# 07_MCU.net
KiCad netlist of a schematic drawn in Altium Designer
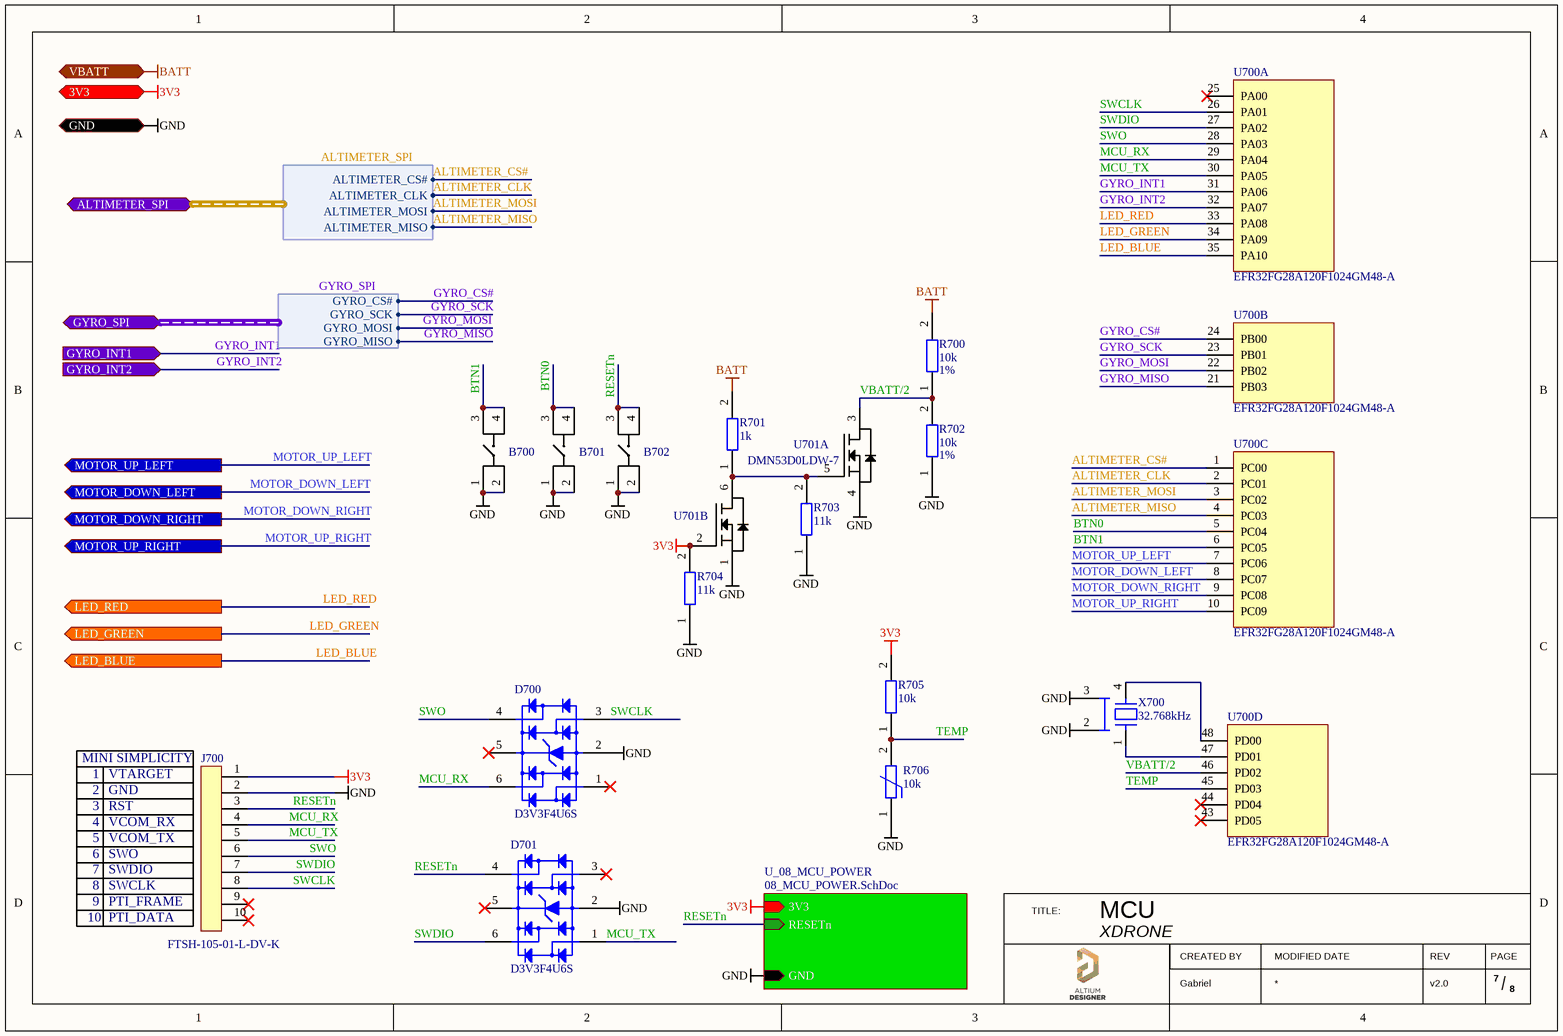
[diagram p0: 07_MCU.SchDoc]

(export (version "E")
  (design (tool "Eeschema 10.0.6"))
  (components
    (comp (ref "B700")
      (value "BTN_1B_PTS647SK38SMTR2LFS")
      (footprint "BTN_SMD")
      (description "Button PTS647SK38SMTR2LFS")
      (fields (field (name "MANUFACTURER") "C&K"))
      (libsource (lib "Connectors") (part "BTN_1B_PTS647SK38SMTR2LFS"))
    )
    (comp (ref "B701")
      (value "BTN_1B_PTS647SK38SMTR2LFS")
      (footprint "BTN_SMD")
      (description "Button PTS647SK38SMTR2LFS")
      (fields (field (name "MANUFACTURER") "C&K"))
      (libsource (lib "Connectors") (part "BTN_1B_PTS647SK38SMTR2LFS"))
    )
    (comp (ref "B702")
      (value "BTN_1B_PTS647SK38SMTR2LFS")
      (footprint "BTN_SMD")
      (description "Button PTS647SK38SMTR2LFS")
      (fields (field (name "MANUFACTURER") "C&K"))
      (libsource (lib "Connectors") (part "BTN_1B_PTS647SK38SMTR2LFS"))
    )
    (comp (ref "D700")
      (value "ESD_D3V3F4U6S")
      (footprint "SOT-363 SC-70-6")
      (description "4 CH ESD PROTECTION SOT363 LOW CAP D3V3F4U6S")
      (fields (field (name "MANUFACTURER") "DIODES INC") (field (name "MANUFACTURER REFERENCE") "D3V3F4U6S"))
      (libsource (lib "Semiconductor") (part "ESD_D3V3F4U6S"))
    )
    (comp (ref "D701")
      (value "ESD_D3V3F4U6S")
      (footprint "SOT-363 SC-70-6")
      (description "4 CH ESD PROTECTION SOT363 LOW CAP D3V3F4U6S")
      (fields (field (name "MANUFACTURER") "DIODES INC") (field (name "MANUFACTURER REFERENCE") "D3V3F4U6S"))
      (libsource (lib "Semiconductor") (part "ESD_D3V3F4U6S"))
    )
    (comp (ref "J700")
      (value "CON_5x2PIN_RA_1.27_FTSH-105-01-L-DV-K")
      (footprint "CON_5x2PIN_RA_FTSH-105-01-L-DV-K")
      (description "CONNECTOR 5x2PIN RA 1.27 PITCH FTSH-105-01-L-DV-K")
      (fields
        (field (name "MANUFACTURER") "SAMTEC")
        (field (name "MANUFACTURER REFERENCE") "FTSH-105-01-L-DV-K")
      )
      (libsource (lib "Connectors") (part "CON_5x2PIN_RA_1.27_FTSH-105-01-L-DV-K"))
    )
    (comp (ref "R700")
      (value "10k")
      (footprint "RES_0402")
      (description "RESISTOR 10k 1% 0402 RC0402FR-0710KL")
      (fields
        (field (name "TOLERANCE") "1%")
        (field (name "MANUFACTURER") "YAGEO")
        (field (name "Comment") "RES_10k_1%_0402_RC0402FR-0710KL")
      )
      (libsource (lib "Resistors") (part "RES_10k_1%_0402_RC0402FR-0710KL"))
    )
    (comp (ref "R701")
      (value "1k")
      (footprint "RES_0402")
      (description "RESISTOR 1k 1% 0402 RC0402FR-071KL")
      (fields (field (name "TOLERANCE") "1%") (field (name "MANUFACTURER") "YAGEO"))
      (libsource (lib "Resistors") (part "RES_1k_1%_0402_RC0402FR-071KL"))
    )
    (comp (ref "R702")
      (value "10k")
      (footprint "RES_0402")
      (description "RESISTOR 10k 1% 0402 RC0402FR-0710KL")
      (fields
        (field (name "TOLERANCE") "1%")
        (field (name "MANUFACTURER") "YAGEO")
        (field (name "Comment") "RES_10k_1%_0402_RC0402FR-0710KL")
      )
      (libsource (lib "Resistors") (part "RES_10k_1%_0402_RC0402FR-0710KL"))
    )
    (comp (ref "R703")
      (value "11k")
      (footprint "RES_0402")
      (description "RESISTOR 11k 5% 0402 ERJ-2GEJ113X")
      (fields (field (name "TOLERANCE") "5%") (field (name "MANUFACTURER") "PANASONIC"))
      (libsource (lib "Resistors") (part "RES_11k_5%_0402_ERJ-2GEJ113X"))
    )
    (comp (ref "R704")
      (value "11k")
      (footprint "RES_0402")
      (description "RESISTOR 11k 5% 0402 ERJ-2GEJ113X")
      (fields (field (name "TOLERANCE") "5%") (field (name "MANUFACTURER") "PANASONIC"))
      (libsource (lib "Resistors") (part "RES_11k_5%_0402_ERJ-2GEJ113X"))
    )
    (comp (ref "R705")
      (value "10k")
      (footprint "RES_0402")
      (description "RESISTOR 10k 1% 0402 RC0402FR-0710KL")
      (fields (field (name "TOLERANCE") "1%") (field (name "MANUFACTURER") "YAGEO"))
      (libsource (lib "Resistors") (part "RES_10k_1%_0402_RC0402FR-0710KL"))
    )
    (comp (ref "R706")
      (value "10k")
      (footprint "RES_0402")
      (description "THERMISTANCE 10k 1% 0402 NTCG103JF103FT1")
      (fields (field (name "TOLERANCE") "1%") (field (name "MANUFACTURER") "TDK"))
      (libsource (lib "Resistors") (part "THER_10k_1%_0402_NTCG103JF103FT1"))
    )
    (comp (ref "U700")
      (value "MCU_1MB_256kB_EFR32FG28A120F1024GM48-A")
      (footprint "QFN48")
      (description "MCU 1MB 256kB EFR32FG28A120F1024GM48-A")
      (fields
        (field (name "MANUFACTURER") "SILICON LABS")
        (field (name "MANUFACTURER REFERENCE") "EFR32FG28A120F1024GM48-A")
      )
      (libsource (lib "Semiconductor") (part "MCU_1MB_256kB_EFR32FG28A120F1024GM48-A"))
    )
    (comp (ref "U701")
      (value "MOS_2G_50VDS_360mA_0.8Vth_DMN53D0LDW-7")
      (footprint "SOT-363 SC-70-6")
      (description "MOS 2GATES 50VDS 360mA 0.8Vth")
      (fields (field (name "MANUFACTURER") "DIODES") (field (name "MANUFACTURER REFERENCE") "DMN53D0LDW-7"))
      (libsource (lib "Semiconductor") (part "MOS_2G_50VDS_360mA_0.8Vth_DMN53D0LDW-7"))
    )
    (comp (ref "X700")
      (value "QUARTZ_32.768kHz_20ppm_830016178")
      (footprint "4-SOJ")
      (description "QUARTZ 32.768kHz 20ppm 830016178")
      (fields
        (field (name "MANUFACTURER") "WURTH")
        (field (name "TOLERANCE") "20 ppm")
        (field (name "FREQUENCY") "32.768kHz")
      )
      (libsource (lib "Oscillators") (part "QUARTZ_32.768kHz_20ppm_830016178"))
    )
  )
  (nets
    (net (code "3") (name "/ALTIMETER_CLK") (class "Default")
      (node (ref "U700") (pin "2") (pinfunction "PC01_2") (pintype "passive"))
    )
    (net (code "4") (name "/ALTIMETER_CS#") (class "Default")
      (node (ref "U700") (pin "1") (pinfunction "PC00_1") (pintype "passive"))
    )
    (net (code "5") (name "/ALTIMETER_MISO") (class "Default")
      (node (ref "U700") (pin "4") (pinfunction "PC03_4") (pintype "passive"))
    )
    (net (code "6") (name "/ALTIMETER_MOSI") (class "Default")
      (node (ref "U700") (pin "3") (pinfunction "PC02_3") (pintype "passive"))
    )
    (net (code "7") (name "/BTN0") (class "Default")
      (node (ref "B701") (pin "3") (pintype "passive"))
      (node (ref "B701") (pin "4") (pintype "passive"))
      (node (ref "U700") (pin "5") (pinfunction "PC04_5") (pintype "passive"))
    )
    (net (code "8") (name "/BTN1") (class "Default")
      (node (ref "B700") (pin "3") (pintype "passive"))
      (node (ref "B700") (pin "4") (pintype "passive"))
      (node (ref "U700") (pin "6") (pinfunction "PC05_6") (pintype "passive"))
    )
    (net (code "9") (name "/GYRO_CS#") (class "Default")
      (node (ref "U700") (pin "24") (pinfunction "PB00_24") (pintype "passive"))
    )
    (net (code "10") (name "/GYRO_INT1") (class "Default")
      (node (ref "U700") (pin "31") (pinfunction "PA06_31") (pintype "passive"))
    )
    (net (code "11") (name "/GYRO_INT2") (class "Default")
      (node (ref "U700") (pin "32") (pinfunction "PA07_32") (pintype "passive"))
    )
    (net (code "12") (name "/GYRO_MISO") (class "Default")
      (node (ref "U700") (pin "21") (pinfunction "PB03_21") (pintype "passive"))
    )
    (net (code "13") (name "/GYRO_MOSI") (class "Default")
      (node (ref "U700") (pin "22") (pinfunction "PB02_22") (pintype "passive"))
    )
    (net (code "14") (name "/GYRO_SCK") (class "Default")
      (node (ref "U700") (pin "23") (pinfunction "PB01_23") (pintype "passive"))
    )
    (net (code "15") (name "/LED_BLUE") (class "Default")
      (node (ref "U700") (pin "35") (pinfunction "PA10_35") (pintype "passive"))
    )
    (net (code "16") (name "/LED_GREEN") (class "Default")
      (node (ref "U700") (pin "34") (pinfunction "PA09_34") (pintype "passive"))
    )
    (net (code "17") (name "/LED_RED") (class "Default")
      (node (ref "U700") (pin "33") (pinfunction "PA08_33") (pintype "passive"))
    )
    (net (code "18") (name "/MCU_RX") (class "Default")
      (node (ref "D700") (pin "6") (pinfunction "6_6") (pintype "passive"))
      (node (ref "J700") (pin "4") (pinfunction "4_4") (pintype "passive"))
      (node (ref "U700") (pin "29") (pinfunction "PA04_29") (pintype "passive"))
    )
    (net (code "19") (name "/MCU_TX") (class "Default")
      (node (ref "D701") (pin "1") (pinfunction "1_1") (pintype "passive"))
      (node (ref "J700") (pin "5") (pinfunction "5_5") (pintype "passive"))
      (node (ref "U700") (pin "30") (pinfunction "PA05_30") (pintype "passive"))
    )
    (net (code "20") (name "/MOTOR_DOWN_LEFT") (class "Default")
      (node (ref "U700") (pin "8") (pinfunction "PC07_8") (pintype "passive"))
    )
    (net (code "21") (name "/MOTOR_DOWN_RIGHT") (class "Default")
      (node (ref "U700") (pin "9") (pinfunction "PC08_9") (pintype "passive"))
    )
    (net (code "22") (name "/MOTOR_UP_LEFT") (class "Default")
      (node (ref "U700") (pin "7") (pinfunction "PC06_7") (pintype "passive"))
    )
    (net (code "23") (name "/MOTOR_UP_RIGHT") (class "Default")
      (node (ref "U700") (pin "10") (pinfunction "PC09_10") (pintype "passive"))
    )
    (net (code "24") (name "/RESETn") (class "Default")
      (node (ref "B702") (pin "3") (pintype "passive"))
      (node (ref "B702") (pin "4") (pintype "passive"))
      (node (ref "D701") (pin "4") (pinfunction "4_4") (pintype "passive"))
      (node (ref "J700") (pin "3") (pinfunction "3_3") (pintype "passive"))
    )
    (net (code "25") (name "/SWCLK") (class "Default")
      (node (ref "D700") (pin "3") (pinfunction "3_3") (pintype "passive"))
      (node (ref "J700") (pin "8") (pinfunction "8_8") (pintype "passive"))
      (node (ref "U700") (pin "26") (pinfunction "PA01_26") (pintype "passive"))
    )
    (net (code "26") (name "/SWDIO") (class "Default")
      (node (ref "D701") (pin "6") (pinfunction "6_6") (pintype "passive"))
      (node (ref "J700") (pin "7") (pinfunction "7_7") (pintype "passive"))
      (node (ref "U700") (pin "27") (pinfunction "PA02_27") (pintype "passive"))
    )
    (net (code "27") (name "/SWO") (class "Default")
      (node (ref "D700") (pin "4") (pinfunction "4_4") (pintype "passive"))
      (node (ref "J700") (pin "6") (pinfunction "6_6") (pintype "passive"))
      (node (ref "U700") (pin "28") (pinfunction "PA03_28") (pintype "passive"))
    )
    (net (code "28") (name "/TEMP") (class "Default")
      (node (ref "R705") (pin "1") (pinfunction "1_1") (pintype "passive"))
      (node (ref "R706") (pin "2") (pinfunction "2_2") (pintype "passive"))
      (node (ref "U700") (pin "45") (pinfunction "PD03_45") (pintype "passive"))
    )
    (net (code "29") (name "/VBATT{slash}2") (class "Default")
      (node (ref "R700") (pin "1") (pinfunction "1_1") (pintype "passive"))
      (node (ref "R702") (pin "2") (pinfunction "2_2") (pintype "passive"))
      (node (ref "U700") (pin "46") (pinfunction "PD02_46") (pintype "passive"))
      (node (ref "U701") (pin "3") (pinfunction "3_3") (pintype "passive"))
    )
    (net (code "32") (name "3V3") (class "Default")
      (node (ref "J700") (pin "1") (pinfunction "1_1") (pintype "passive"))
      (node (ref "R704") (pin "2") (pinfunction "2_2") (pintype "passive"))
      (node (ref "R705") (pin "2") (pinfunction "2_2") (pintype "passive"))
      (node (ref "U701") (pin "2") (pinfunction "2_2") (pintype "passive"))
    )
    (net (code "33") (name "BATT") (class "Default")
      (node (ref "R700") (pin "2") (pinfunction "2_2") (pintype "passive"))
      (node (ref "R701") (pin "2") (pinfunction "2_2") (pintype "passive"))
    )
    (net (code "34") (name "GND") (class "Default")
      (node (ref "B700") (pin "1") (pintype "passive"))
      (node (ref "B700") (pin "2") (pintype "passive"))
      (node (ref "B701") (pin "1") (pintype "passive"))
      (node (ref "B701") (pin "2") (pintype "passive"))
      (node (ref "B702") (pin "1") (pintype "passive"))
      (node (ref "B702") (pin "2") (pintype "passive"))
      (node (ref "D700") (pin "2") (pinfunction "2_2") (pintype "passive"))
      (node (ref "D701") (pin "2") (pinfunction "2_2") (pintype "passive"))
      (node (ref "J700") (pin "2") (pinfunction "2_2") (pintype "passive"))
      (node (ref "R702") (pin "1") (pinfunction "1_1") (pintype "passive"))
      (node (ref "R703") (pin "1") (pinfunction "1_1") (pintype "passive"))
      (node (ref "R704") (pin "1") (pinfunction "1_1") (pintype "passive"))
      (node (ref "R706") (pin "1") (pinfunction "1_1") (pintype "passive"))
      (node (ref "U701") (pin "1") (pinfunction "1_1") (pintype "passive"))
      (node (ref "U701") (pin "4") (pinfunction "4_4") (pintype "passive"))
      (node (ref "X700") (pin "2") (pinfunction "2_2") (pintype "passive"))
      (node (ref "X700") (pin "3") (pinfunction "3_3") (pintype "passive"))
    )
    (net (code "35") (name "Net-(R701-Pad1)") (class "Default")
      (node (ref "R701") (pin "1") (pinfunction "1_1") (pintype "passive"))
      (node (ref "R703") (pin "2") (pinfunction "2_2") (pintype "passive"))
      (node (ref "U701") (pin "5") (pinfunction "5_5") (pintype "passive"))
      (node (ref "U701") (pin "6") (pinfunction "6_6") (pintype "passive"))
    )
    (net (code "36") (name "Net-(U700D-PD00)") (class "Default")
      (node (ref "U700") (pin "48") (pinfunction "PD00_48") (pintype "passive"))
      (node (ref "X700") (pin "4") (pinfunction "4_4") (pintype "passive"))
    )
    (net (code "37") (name "Net-(U700D-PD01)") (class "Default")
      (node (ref "U700") (pin "47") (pinfunction "PD01_47") (pintype "passive"))
      (node (ref "X700") (pin "1") (pinfunction "1_1") (pintype "passive"))
    )
    (net (code "38") (name "unconnected-(D700-Pad1)") (class "Default")
      (node (ref "D700") (pin "1") (pinfunction "1_1") (pintype "passive+no_connect"))
    )
    (net (code "39") (name "unconnected-(D700-Pad5)") (class "Default")
      (node (ref "D700") (pin "5") (pinfunction "5_5") (pintype "passive+no_connect"))
    )
    (net (code "40") (name "unconnected-(D701-Pad3)") (class "Default")
      (node (ref "D701") (pin "3") (pinfunction "3_3") (pintype "passive+no_connect"))
    )
    (net (code "41") (name "unconnected-(D701-Pad5)") (class "Default")
      (node (ref "D701") (pin "5") (pinfunction "5_5") (pintype "passive+no_connect"))
    )
    (net (code "42") (name "unconnected-(J700-Pad9)") (class "Default")
      (node (ref "J700") (pin "9") (pinfunction "9_9") (pintype "passive+no_connect"))
    )
    (net (code "43") (name "unconnected-(J700-Pad10)") (class "Default")
      (node (ref "J700") (pin "10") (pinfunction "10_10") (pintype "passive+no_connect"))
    )
    (net (code "44") (name "unconnected-(U700A-PA00-Pad25)") (class "Default")
      (node (ref "U700") (pin "25") (pinfunction "PA00_25") (pintype "passive+no_connect"))
    )
    (net (code "45") (name "unconnected-(U700D-PD04-Pad44)") (class "Default")
      (node (ref "U700") (pin "44") (pinfunction "PD04_44") (pintype "passive+no_connect"))
    )
    (net (code "46") (name "unconnected-(U700D-PD05-Pad43)") (class "Default")
      (node (ref "U700") (pin "43") (pinfunction "PD05_43") (pintype "passive+no_connect"))
    )
  )
)
